# FLYBACK_SWITCHING_POWER_SUPPLY_V1_2.net
KiCad netlist of a schematic drawn in Altium Designer
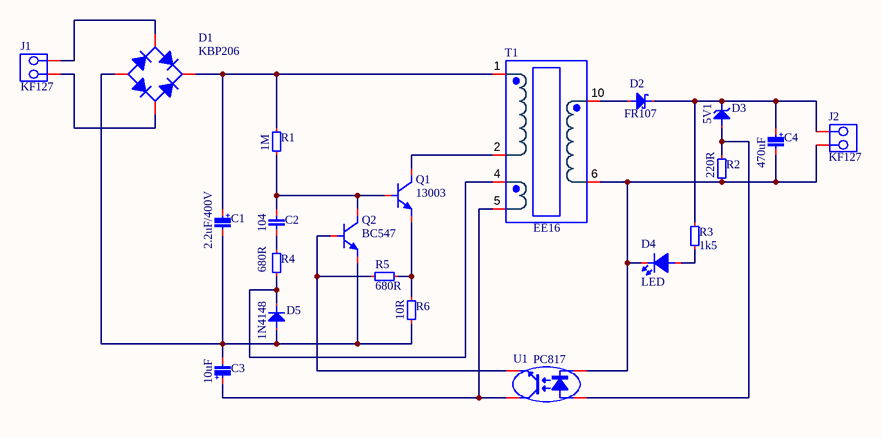
[diagram p0: FLYBACK_SWITCHING_POWER_SUPPLY_V1_2.SchDoc]

(export (version "E")
  (design (tool "Eeschema 10.0.6"))
  (components
    (comp (ref "C1")
      (value "2.2uF/400V")
      (footprint "CAP_RAD_D10x12.5")
      (libsource (lib "MyAltiumLibrary") (part "Capacitor(Radian)"))
    )
    (comp (ref "C2")
      (value "104")
      (footprint "CAP_Ceramic_2.5MM")
      (libsource (lib "MyAltiumLibrary") (part "Capacitors(Disc)"))
    )
    (comp (ref "C3")
      (value "10uF")
      (footprint "CAP_RAD_D05x11")
      (libsource (lib "") (part "Capacitor(Radian)_1"))
    )
    (comp (ref "C4")
      (value "470uF")
      (footprint "CAP_RAD_D06.3x11")
      (libsource (lib "MyAltiumLibrary") (part "Capacitor(Radian)"))
    )
    (comp (ref "D1")
      (value "KBP206")
      (footprint "DIODE-KBP206")
      (libsource (lib "MyAltiumLibrary") (part "Diode-KBP206"))
    )
    (comp (ref "D2")
      (value "FR107")
      (footprint "DO-204AL-BK")
      (description "1A 1000V")
      (libsource (lib "MyAltiumLibrary") (part "Diode-FR107"))
    )
    (comp (ref "D3")
      (value "5V1")
      (footprint "DO-204AL-RD")
      (libsource (lib "MyAltiumLibrary") (part "Diode-Zener"))
    )
    (comp (ref "D4") (value "LED") (footprint "LED_5MM") (libsource (lib "MyAltiumLibrary") (part "LED 5MM")))
    (comp (ref "D5")
      (value "1N4148")
      (footprint "DO-204AH-RD")
      (description "The fast switching diode")
      (libsource (lib "MyAltiumLibrary") (part "Diode-1N4148"))
    )
    (comp (ref "J1")
      (value "KF127")
      (footprint "DG127-5.0-02P-14-00AH")
      (libsource (lib "") (part "DG127-5.0-02P-14-00AH_1"))
    )
    (comp (ref "J2")
      (value "KF127")
      (footprint "DG127-5.0-02P-14-00AH")
      (libsource (lib "MyAltiumLibrary") (part "DG127-5.0-02P-14-00AH"))
    )
    (comp (ref "Q1")
      (value "13003")
      (footprint "TO-126")
      (libsource (lib "MyAltiumLibrary") (part "Transistor-MJE13003"))
    )
    (comp (ref "Q2")
      (value "BC547")
      (footprint "TO-92")
      (description "VCEO: 45 Vdc\r\nVCBO: 50 Vdc\r\nVEBO: 6.0 Vdc")
      (libsource (lib "MyAltiumLibrary") (part "Transistor-BC547"))
    )
    (comp (ref "R1") (value "1M") (footprint "RES-0.25W-H") (libsource (lib "") (part "Resistors THD_1")))
    (comp (ref "R2")
      (value "220R")
      (footprint "RES-0.25W-H")
      (libsource (lib "MyAltiumLibrary") (part "Resistors THD"))
    )
    (comp (ref "R3") (value "1k5") (footprint "RES-0.25W-H") (libsource (lib "") (part "Resistors THD_1")))
    (comp (ref "R4") (value "680R") (footprint "RES-0.25W-H") (libsource (lib "") (part "Resistors THD_1")))
    (comp (ref "R5") (value "680R") (footprint "RES-0.25W-H") (libsource (lib "") (part "Resistors THD_2")))
    (comp (ref "R6")
      (value "10R")
      (footprint "RES-0.5W-V")
      (libsource (lib "MyAltiumLibrary") (part "Resistors THD"))
    )
    (comp (ref "T1")
      (value "EE16")
      (footprint "TRANSFORMERS-EE16(5+5)-H")
      (libsource (lib "MyAltiumLibrary") (part "TRANS-EE16-HORIZONTAL(5+5)"))
    )
    (comp (ref "U1")
      (value "PC817")
      (footprint "PC817-DIP")
      (libsource (lib "MyAltiumLibrary") (part "Opto-PC817"))
    )
  )
  (nets
    (net (code "1") (name "Net-(C2-Pad1)") (class "Default")
      (node (ref "C2") (pin "1") (pinfunction "1_1") (pintype "passive"))
      (node (ref "R4") (pin "2") (pinfunction "2_2") (pintype "passive"))
    )
    (net (code "2") (name "Net-(C4-Pad1)") (class "Default")
      (node (ref "C4") (pin "1") (pinfunction "1_1") (pintype "passive"))
      (node (ref "D2") (pin "2") (pinfunction "2_2") (pintype "passive"))
      (node (ref "D3") (pin "2") (pinfunction "2_2") (pintype "passive"))
      (node (ref "J2") (pin "1") (pinfunction "1_1") (pintype "passive"))
      (node (ref "R3") (pin "2") (pinfunction "2_2") (pintype "passive"))
    )
    (net (code "3") (name "Net-(D1-+)") (class "Default")
      (node (ref "C1") (pin "1") (pinfunction "1_1") (pintype "passive"))
      (node (ref "D1") (pin "1") (pinfunction "+_1") (pintype "passive"))
      (node (ref "R1") (pin "2") (pinfunction "2_2") (pintype "passive"))
      (node (ref "T1") (pin "1") (pinfunction "1_1") (pintype "passive"))
    )
    (net (code "4") (name "Net-(D1--)") (class "Default")
      (node (ref "C1") (pin "2") (pinfunction "2_2") (pintype "passive"))
      (node (ref "C3") (pin "2") (pinfunction "2_2") (pintype "passive"))
      (node (ref "D1") (pin "4") (pinfunction "-_4") (pintype "passive"))
      (node (ref "D5") (pin "1") (pinfunction "1_1") (pintype "passive"))
      (node (ref "Q2") (pin "3") (pinfunction "E_3") (pintype "passive"))
      (node (ref "R6") (pin "2") (pinfunction "2_2") (pintype "passive"))
    )
    (net (code "5") (name "Net-(D1-AC-Pad2)") (class "Default")
      (node (ref "D1") (pin "2") (pinfunction "AC_2") (pintype "passive"))
      (node (ref "J1") (pin "2") (pinfunction "2_2") (pintype "passive"))
    )
    (net (code "6") (name "Net-(D1-AC-Pad3)") (class "Default")
      (node (ref "D1") (pin "3") (pinfunction "AC_3") (pintype "passive"))
      (node (ref "J1") (pin "1") (pinfunction "1_1") (pintype "passive"))
    )
    (net (code "7") (name "Net-(D2-Pad1)") (class "Default")
      (node (ref "D2") (pin "1") (pinfunction "1_1") (pintype "passive"))
      (node (ref "T1") (pin "10") (pinfunction "10_10") (pintype "passive"))
    )
    (net (code "8") (name "Net-(D4-A)") (class "Default")
      (node (ref "D4") (pin "1") (pinfunction "A_1") (pintype "passive"))
      (node (ref "R3") (pin "1") (pinfunction "1_1") (pintype "passive"))
    )
    (net (code "9") (name "Net-(D4-K)") (class "Default")
      (node (ref "C4") (pin "2") (pinfunction "2_2") (pintype "passive"))
      (node (ref "D4") (pin "2") (pinfunction "K_2") (pintype "passive"))
      (node (ref "J2") (pin "2") (pinfunction "2_2") (pintype "passive"))
      (node (ref "R2") (pin "2") (pinfunction "2_2") (pintype "passive"))
      (node (ref "T1") (pin "6") (pinfunction "6_6") (pintype "passive"))
      (node (ref "U1") (pin "2") (pinfunction "K_2") (pintype "passive"))
    )
    (net (code "10") (name "Net-(D5-Pad2)") (class "Default")
      (node (ref "D5") (pin "2") (pinfunction "2_2") (pintype "passive"))
      (node (ref "R4") (pin "1") (pinfunction "1_1") (pintype "passive"))
      (node (ref "T1") (pin "4") (pinfunction "4_4") (pintype "passive"))
    )
    (net (code "11") (name "Net-(Q1-B)") (class "Default")
      (node (ref "C2") (pin "2") (pinfunction "2_2") (pintype "passive"))
      (node (ref "Q1") (pin "1") (pinfunction "B_1") (pintype "passive"))
      (node (ref "Q2") (pin "1") (pinfunction "C_1") (pintype "passive"))
      (node (ref "R1") (pin "1") (pinfunction "1_1") (pintype "passive"))
    )
    (net (code "12") (name "Net-(Q1-C)") (class "Default")
      (node (ref "Q1") (pin "2") (pinfunction "C_2") (pintype "passive"))
      (node (ref "T1") (pin "2") (pinfunction "2_2") (pintype "passive"))
    )
    (net (code "13") (name "Net-(Q1-E)") (class "Default")
      (node (ref "Q1") (pin "3") (pinfunction "E_3") (pintype "passive"))
      (node (ref "R5") (pin "1") (pinfunction "1_1") (pintype "passive"))
      (node (ref "R6") (pin "1") (pinfunction "1_1") (pintype "passive"))
    )
    (net (code "14") (name "Net-(Q2-B)") (class "Default")
      (node (ref "Q2") (pin "2") (pinfunction "B_2") (pintype "passive"))
      (node (ref "R5") (pin "2") (pinfunction "2_2") (pintype "passive"))
      (node (ref "U1") (pin "3") (pinfunction "E_3") (pintype "passive"))
    )
    (net (code "15") (name "Net-(U1-A)") (class "Default")
      (node (ref "D3") (pin "1") (pinfunction "1_1") (pintype "passive"))
      (node (ref "R2") (pin "1") (pinfunction "1_1") (pintype "passive"))
      (node (ref "U1") (pin "1") (pinfunction "A_1") (pintype "passive"))
    )
    (net (code "16") (name "Net-(U1-C)") (class "Default")
      (node (ref "C3") (pin "1") (pinfunction "1_1") (pintype "passive"))
      (node (ref "T1") (pin "5") (pinfunction "5_5") (pintype "passive"))
      (node (ref "U1") (pin "4") (pinfunction "C_4") (pintype "passive"))
    )
  )
)
